# 07-TCXO_Crystal.net
KiCad netlist of a schematic drawn in Altium Designer
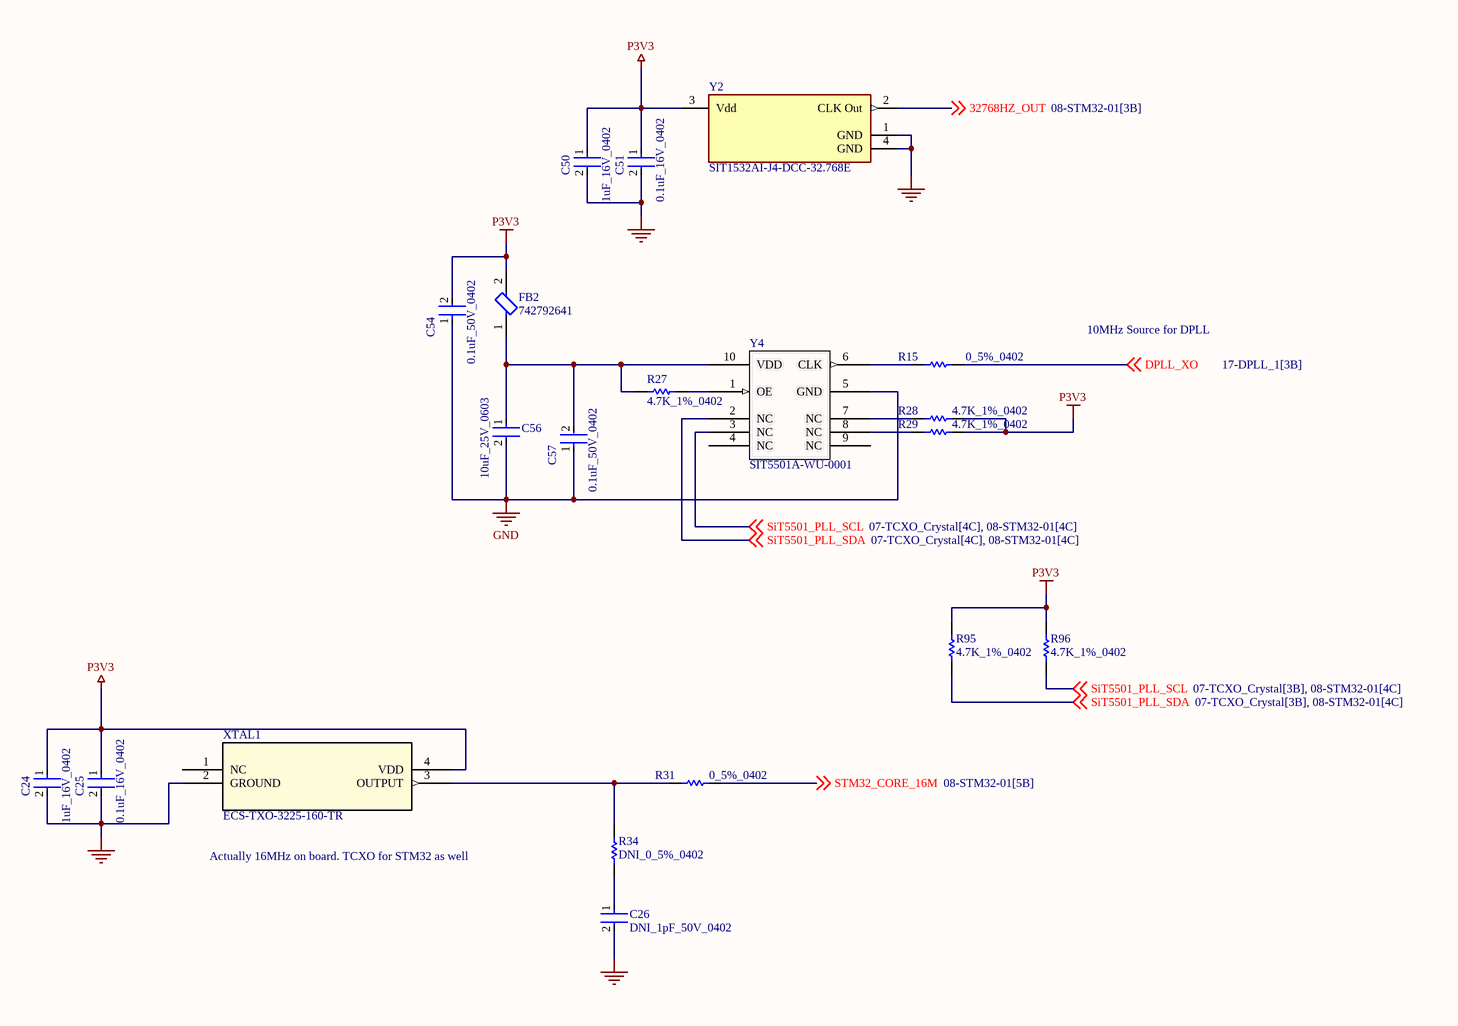
[diagram p0: 07-TCXO_Crystal.SchDoc]

(export (version "E")
  (design (tool "Eeschema 10.0.6"))
  (components
    (comp (ref "C24")
      (value "1uF_16V_0402")
      (footprint "FP-0402-L_1_0_0_05-W_0_5-IPC_A")
      (description "None")
      (fields (field (name "TOLERANCE") "10%"))
      (libsource (lib "Altium Content Vault") (part "b4654b650e69147ec39a6b967a45e02"))
    )
    (comp (ref "C25")
      (value "0.1uF_16V_0402")
      (footprint "FP-C0402-BB-MFG")
      (description "CAP CER 0.1UF 16V 5% X7R 0402")
      (fields
        (field (name "MANUFACTURER") "Kemet")
        (field (name "MANUFACTURER PART NUMBER") "C0402C104J4RACTU")
      )
      (libsource (lib "Altium Content Vault") (part "b4654b650e69147ec39a6b967a45e02"))
    )
    (comp (ref "C26")
      (value "DNI_1pF_50V_0402")
      (footprint "FP-GJM155-0_05-IPC_B")
      (description "Multi-Layer Ceramic Capacitor 1pF C0G  ±0.1pF 0402 Paper T/R")
      (fields (field (name "VOLTAGE") "50V"))
      (libsource (lib "Altium Content Vault") (part "02cd4be3c70576c341d710602a673aa"))
    )
    (comp (ref "C50")
      (value "1uF_16V_0402")
      (footprint "FP-0402-L_1_0_0_05-W_0_5-IPC_A")
      (description "None")
      (fields (field (name "TOLERANCE") "10%"))
      (libsource (lib "Altium Content Vault") (part "b4654b650e69147ec39a6b967a45e02"))
    )
    (comp (ref "C51")
      (value "0.1uF_16V_0402")
      (footprint "FP-C0402-BB-MFG")
      (description "CAP CER 0.1UF 16V 5% X7R 0402")
      (fields
        (field (name "MANUFACTURER") "Kemet")
        (field (name "MANUFACTURER PART NUMBER") "C0402C104J4RACTU")
      )
      (libsource (lib "Altium Content Vault") (part "b4654b650e69147ec39a6b967a45e02"))
    )
    (comp (ref "C54")
      (value "0.1uF_50V_0402")
      (footprint "FP-C1005-050-0_05-IPC_C")
      (description "Multilayer Ceramic Capacitors 100nF ±10% 50V X7R SMD 0402")
      (fields (field (name "VOLTAGE") "50V") (field (name "TOLERANCE") "10%"))
      (libsource (lib "Altium Content Vault") (part "b4654b650e69147ec39a6b967a45e02"))
    )
    (comp (ref "C56")
      (value "10uF_25V_0603")
      (footprint "FP-CL10-IPC_C")
      (description "Cap Ceramic 10uF 25V X5R ±20% Pad SMD 0603 +85°C T/R")
      (fields (field (name "TOLERANCE") "20%"))
      (libsource (lib "Altium Content Vault") (part "b4654b650e69147ec39a6b967a45e02"))
    )
    (comp (ref "C57")
      (value "0.1uF_50V_0402")
      (footprint "FP-C1005-050-0_05-IPC_C")
      (description "Multilayer Ceramic Capacitors 100nF ±10% 50V X7R SMD 0402")
      (fields (field (name "VOLTAGE") "50V") (field (name "TOLERANCE") "10%"))
      (libsource (lib "Altium Content Vault") (part "b4654b650e69147ec39a6b967a45e02"))
    )
    (comp (ref "FB2")
      (value "742792641")
      (footprint "FP-742792641-MFG")
      (description "FERRITE BEAD 300 OHM 0603 1LN")
      (fields (field (name "TOLERANCE") "25%"))
      (libsource (lib "Altium Content Vault") (part "5f30dd21d616792df468990f7003faa"))
    )
    (comp (ref "R15")
      (value "0_5%_0402")
      (footprint "RESC1005X40X25NL05T10")
      (fields (field (name "MANUFACTURER") "Panasonic") (field (name "PART NUMBER") "ERJ-U020R00X"))
      (libsource (lib "Altium Content Vault") (part "RES"))
    )
    (comp (ref "R27")
      (value "4.7K_1%_0402")
      (footprint "RESC1005X40X25NL10T10")
      (fields (field (name "MANUFACTURER") "Bourns") (field (name "PART NUMBER") "CR0402-FX-4701GLF"))
      (libsource (lib "Altium Content Vault") (part "RES"))
    )
    (comp (ref "R28")
      (value "4.7K_1%_0402")
      (footprint "RESC1005X40X25NL10T10")
      (fields (field (name "MANUFACTURER") "Bourns") (field (name "PART NUMBER") "CR0402-FX-4701GLF"))
      (libsource (lib "Altium Content Vault") (part "RES"))
    )
    (comp (ref "R29")
      (value "4.7K_1%_0402")
      (footprint "RESC1005X40X25NL10T10")
      (fields (field (name "MANUFACTURER") "Bourns") (field (name "PART NUMBER") "CR0402-FX-4701GLF"))
      (libsource (lib "Altium Content Vault") (part "RES"))
    )
    (comp (ref "R31")
      (value "0_5%_0402")
      (footprint "RESC1005X40X25NL05T10")
      (fields (field (name "MANUFACTURER") "Panasonic") (field (name "PART NUMBER") "ERJ-U020R00X"))
      (libsource (lib "Altium Content Vault") (part "RES"))
    )
    (comp (ref "R34")
      (value "DNI_0_5%_0402")
      (footprint "RESC1005X40X25NL05T10")
      (fields (field (name "MANUFACTURER") "Panasonic") (field (name "PART NUMBER") "ERJ-U020R00X"))
      (libsource (lib "Altium Content Vault") (part "RES"))
    )
    (comp (ref "R95")
      (value "4.7K_1%_0402")
      (footprint "RESC1005X40X25NL10T10")
      (fields (field (name "MANUFACTURER") "Bourns") (field (name "PART NUMBER") "CR0402-FX-4701GLF"))
      (libsource (lib "Altium Content Vault") (part "RES"))
    )
    (comp (ref "R96")
      (value "4.7K_1%_0402")
      (footprint "RESC1005X40X25NL10T10")
      (fields (field (name "MANUFACTURER") "Bourns") (field (name "PART NUMBER") "CR0402-FX-4701GLF"))
      (libsource (lib "Altium Content Vault") (part "RES"))
    )
    (comp (ref "XTAL1")
      (value "ECS-TXO-3225-160-TR")
      (footprint "ECS-TXO-3225_ECS")
      (description "No Description Available")
      (libsource (lib "ECS-TXO-3225-122P8-TR") (part "ECS-TXO-3225-122.8-TR"))
    )
    (comp (ref "Y2")
      (value "SIT1532AI-J4-DCC-32.768E")
      (footprint "FP-SIT1532-MFG")
      (description "MEMS OSC XO 32.7680KHZ LVCMOS")
      (libsource (lib "Altium Content Vault") (part "c4f9b1365e25d15033dfe34c89f26e6"))
    )
    (comp (ref "Y4")
      (value "SIT5501A-WU-0001")
      (footprint "SITIME_SPL-086-CQFN-010-C07050_REV_DRAFT")
      (description "OSC, MEMS, STRATUM 3E, 10.000MHZ, 10PPB STAB, LVCMOS, 3.3V, O/P EN, 7.0X5.0X2.2MM, CQFN-10")
      (fields (field (name "MANUFACTURER") "SiTime"))
      (libsource (lib "OCXO_DaughterCard") (part "CMP-OSC-00029-2"))
    )
  )
  (nets
    (net (code "1") (name "32768HZ_OUT") (class "Default")
      (node (ref "Y2") (pin "2") (pinfunction "CLK_Out_2") (pintype "output"))
    )
    (net (code "2") (name "DPLL_XO") (class "Default")
      (node (ref "R15") (pin "2") (pinfunction "2_2") (pintype "passive"))
    )
    (net (code "3") (name "GND") (class "Default")
      (node (ref "C24") (pin "2") (pinfunction "2_2") (pintype "passive"))
      (node (ref "C25") (pin "2") (pinfunction "2_2") (pintype "passive"))
      (node (ref "C26") (pin "2") (pinfunction "2_2") (pintype "passive"))
      (node (ref "C50") (pin "2") (pinfunction "2_2") (pintype "passive"))
      (node (ref "C51") (pin "2") (pinfunction "2_2") (pintype "passive"))
      (node (ref "C54") (pin "1") (pinfunction "1_1") (pintype "passive"))
      (node (ref "C56") (pin "2") (pinfunction "2_2") (pintype "passive"))
      (node (ref "C57") (pin "1") (pinfunction "1_1") (pintype "passive"))
      (node (ref "XTAL1") (pin "2") (pinfunction "GROUND_2") (pintype "power_in"))
      (node (ref "Y2") (pin "1") (pinfunction "GND_1") (pintype "power_in"))
      (node (ref "Y2") (pin "4") (pinfunction "GND_4") (pintype "power_in"))
      (node (ref "Y4") (pin "5") (pinfunction "GND_5") (pintype "power_in"))
    )
    (net (code "4") (name "Net-(C26-Pad1)") (class "Default")
      (node (ref "C26") (pin "1") (pinfunction "1_1") (pintype "passive"))
      (node (ref "R34") (pin "1") (pinfunction "1_1") (pintype "passive"))
    )
    (net (code "5") (name "Net-(R28-Pad1)") (class "Default")
      (node (ref "R28") (pin "1") (pinfunction "1_1") (pintype "passive"))
      (node (ref "Y4") (pin "7") (pinfunction "NC_7") (pintype "passive"))
    )
    (net (code "6") (name "Net-(R29-Pad1)") (class "Default")
      (node (ref "R29") (pin "1") (pinfunction "1_1") (pintype "passive"))
      (node (ref "Y4") (pin "8") (pinfunction "NC_8") (pintype "passive"))
    )
    (net (code "7") (name "Net-(XTAL1-OUTPUT)") (class "Default")
      (node (ref "R31") (pin "1") (pinfunction "1_1") (pintype "passive"))
      (node (ref "R34") (pin "2") (pinfunction "2_2") (pintype "passive"))
      (node (ref "XTAL1") (pin "3") (pinfunction "OUTPUT_3") (pintype "output"))
    )
    (net (code "8") (name "Net-(Y4-CLK)") (class "Default")
      (node (ref "R15") (pin "1") (pinfunction "1_1") (pintype "passive"))
      (node (ref "Y4") (pin "6") (pinfunction "CLK_6") (pintype "output"))
    )
    (net (code "9") (name "Net-(Y4-OE)") (class "Default")
      (node (ref "R27") (pin "2") (pinfunction "2_2") (pintype "passive"))
      (node (ref "Y4") (pin "1") (pinfunction "OE_1") (pintype "input"))
    )
    (net (code "10") (name "Net-(Y4-VDD)") (class "Default")
      (node (ref "C56") (pin "1") (pinfunction "1_1") (pintype "passive"))
      (node (ref "C57") (pin "2") (pinfunction "2_2") (pintype "passive"))
      (node (ref "FB2") (pin "1") (pinfunction "1_1") (pintype "passive"))
      (node (ref "R27") (pin "1") (pinfunction "1_1") (pintype "passive"))
      (node (ref "Y4") (pin "10") (pinfunction "VDD_10") (pintype "power_in"))
    )
    (net (code "11") (name "P3V3") (class "Default")
      (node (ref "C24") (pin "1") (pinfunction "1_1") (pintype "passive"))
      (node (ref "C25") (pin "1") (pinfunction "1_1") (pintype "passive"))
      (node (ref "C50") (pin "1") (pinfunction "1_1") (pintype "passive"))
      (node (ref "C51") (pin "1") (pinfunction "1_1") (pintype "passive"))
      (node (ref "C54") (pin "2") (pinfunction "2_2") (pintype "passive"))
      (node (ref "FB2") (pin "2") (pinfunction "2_2") (pintype "passive"))
      (node (ref "R28") (pin "2") (pinfunction "2_2") (pintype "passive"))
      (node (ref "R29") (pin "2") (pinfunction "2_2") (pintype "passive"))
      (node (ref "R95") (pin "2") (pinfunction "2_2") (pintype "passive"))
      (node (ref "R96") (pin "2") (pinfunction "2_2") (pintype "passive"))
      (node (ref "XTAL1") (pin "4") (pinfunction "VDD_4") (pintype "power_in"))
      (node (ref "Y2") (pin "3") (pinfunction "Vdd_3") (pintype "power_in"))
    )
    (net (code "12") (name "STM32_CORE_16M") (class "Default")
      (node (ref "R31") (pin "2") (pinfunction "2_2") (pintype "passive"))
    )
    (net (code "13") (name "SiT5501_PLL_SCL") (class "Default")
      (node (ref "R96") (pin "1") (pinfunction "1_1") (pintype "passive"))
      (node (ref "Y4") (pin "3") (pinfunction "NC_3") (pintype "passive"))
    )
    (net (code "14") (name "SiT5501_PLL_SDA") (class "Default")
      (node (ref "R95") (pin "1") (pinfunction "1_1") (pintype "passive"))
      (node (ref "Y4") (pin "2") (pinfunction "NC_2") (pintype "passive"))
    )
    (net (code "15") (name "unconnected-(XTAL1-NC-Pad1)") (class "Default")
      (node (ref "XTAL1") (pin "1") (pinfunction "NC_1") (pintype "passive"))
    )
    (net (code "16") (name "unconnected-(Y4-NC-Pad4)") (class "Default")
      (node (ref "Y4") (pin "4") (pinfunction "NC_4") (pintype "passive"))
    )
    (net (code "17") (name "unconnected-(Y4-NC-Pad9)") (class "Default")
      (node (ref "Y4") (pin "9") (pinfunction "NC_9") (pintype "passive"))
    )
  )
)
